# ADL5390board.net
KiCad netlist of a schematic drawn in EAGLE
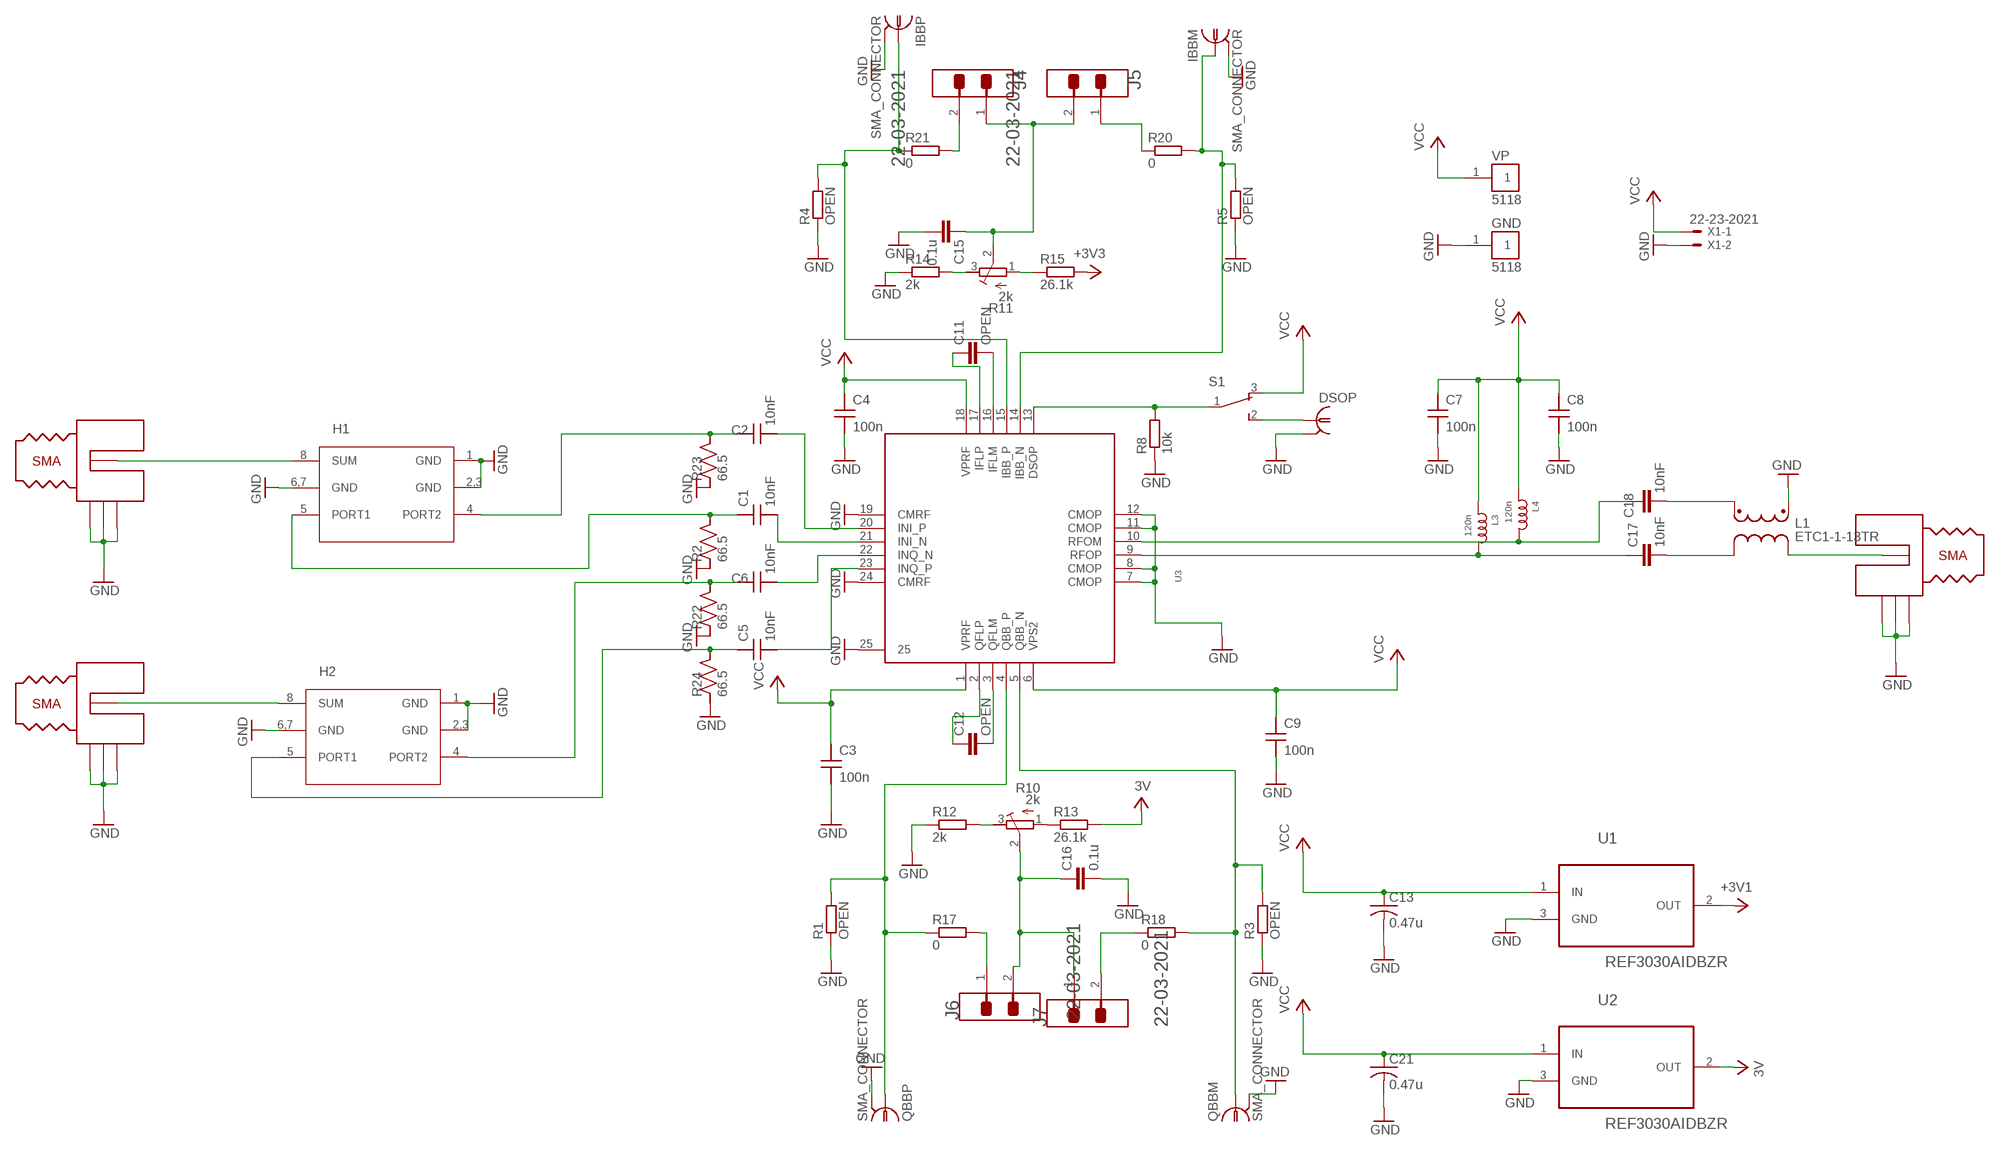
[diagram p0: schematic, sheet 1]

(export (version "E")
  (design (tool "Eeschema 10.0.6"))
  (components
    (comp (ref "C1")
      (value "10nF")
      (footprint "eagle-import:C_MLCC_0402")
      (fields (field (name "PARTNO") "C1005C0G1H102J050BA"))
      (libsource (lib "eagle-import") (part "C_MLCC_SMDCMLCC_0402"))
    )
    (comp (ref "C2")
      (value "10nF")
      (footprint "eagle-import:C_MLCC_0402")
      (fields (field (name "PARTNO") "C1005C0G1H102J050BA"))
      (libsource (lib "eagle-import") (part "C_MLCC_SMDCMLCC_0402"))
    )
    (comp (ref "C3")
      (value "100n")
      (footprint "eagle-import:C_MLCC_0204")
      (fields (field (name "PARTNO") "EWK105C6104MPHF"))
      (libsource (lib "eagle-import") (part "C_MLCC_SMDCMLCC_0204"))
    )
    (comp (ref "C4")
      (value "100n")
      (footprint "eagle-import:C_MLCC_0204")
      (fields (field (name "PARTNO") "EWK105C6104MPHF"))
      (libsource (lib "eagle-import") (part "C_MLCC_SMDCMLCC_0204"))
    )
    (comp (ref "C5")
      (value "10nF")
      (footprint "eagle-import:C_MLCC_0402")
      (fields (field (name "PARTNO") "C1005C0G1H102J050BA"))
      (libsource (lib "eagle-import") (part "C_MLCC_SMDCMLCC_0402"))
    )
    (comp (ref "C6")
      (value "10nF")
      (footprint "eagle-import:C_MLCC_0402")
      (fields (field (name "PARTNO") "C1005C0G1H102J050BA"))
      (libsource (lib "eagle-import") (part "C_MLCC_SMDCMLCC_0402"))
    )
    (comp (ref "C7")
      (value "100n")
      (footprint "eagle-import:C_MLCC_0204")
      (fields (field (name "PARTNO") "EWK105C6104MPHF"))
      (libsource (lib "eagle-import") (part "C_MLCC_SMDCMLCC_0204"))
    )
    (comp (ref "C8")
      (value "100n")
      (footprint "eagle-import:C_MLCC_0204")
      (fields (field (name "PARTNO") "EWK105C6104MPHF"))
      (libsource (lib "eagle-import") (part "C_MLCC_SMDCMLCC_0204"))
    )
    (comp (ref "C9")
      (value "100n")
      (footprint "eagle-import:C_MLCC_0204")
      (fields (field (name "PARTNO") "EWK105C6104MPHF"))
      (libsource (lib "eagle-import") (part "C_MLCC_SMDCMLCC_0204"))
    )
    (comp (ref "C11")
      (value "OPEN")
      (footprint "eagle-import:C0603")
      (libsource (lib "eagle-import") (part "C-EUC0603"))
    )
    (comp (ref "C12")
      (value "OPEN")
      (footprint "eagle-import:C0603")
      (libsource (lib "eagle-import") (part "C-EUC0603"))
    )
    (comp (ref "C13")
      (value "0.47u")
      (footprint "eagle-import:C0603")
      (fields (field (name "PARTNO") "CL10B474KA8NFNC"))
      (libsource (lib "eagle-import") (part "C-USC0603"))
    )
    (comp (ref "C15")
      (value "0.1u")
      (footprint "eagle-import:C0603")
      (fields (field (name "PARTNO") "CL10B104KA8NNNC"))
      (libsource (lib "eagle-import") (part "C-EUC0603"))
    )
    (comp (ref "C16")
      (value "0.1u")
      (footprint "eagle-import:C0603")
      (fields (field (name "PARTNO") "CL10B104KA8NNNC"))
      (libsource (lib "eagle-import") (part "C-EUC0603"))
    )
    (comp (ref "C17")
      (value "10nF")
      (footprint "eagle-import:C0402")
      (fields (field (name "PARTNO") "C1005C0G1H102J050BA"))
      (libsource (lib "eagle-import") (part "C-EUC0402"))
    )
    (comp (ref "C18")
      (value "10nF")
      (footprint "eagle-import:C0402")
      (fields (field (name "PARTNO") "C1005C0G1H102J050BA"))
      (libsource (lib "eagle-import") (part "C-EUC0402"))
    )
    (comp (ref "C21")
      (value "0.47u")
      (footprint "eagle-import:C0603")
      (fields (field (name "PARTNO") "CL10B474KA8NFNC"))
      (libsource (lib "eagle-import") (part "C-USC0603"))
    )
    (comp (ref "DSOP")
      (value "SMA_CONNECTOR")
      (footprint "eagle-import:QKDLAB_JOSH_MECHANICAL_JOHNSON_SMA_EDGE_LAUNCH_142-0701-851")
      (libsource (lib "eagle-import") (part "SMA_CONNECTOR"))
    )
    (comp (ref "GND")
      (value "5118")
      (footprint "eagle-import:TP_5118")
      (fields (field (name "MF") "Keystone Electronics"))
      (libsource (lib "eagle-import") (part "5118"))
    )
    (comp (ref "H1")
      (value "SYPJ-2-33+")
      (footprint "eagle-import:PL-274")
      (libsource (lib "eagle-import") (part "SYPJ-2-33+"))
    )
    (comp (ref "H2")
      (value "SYPJ-2-33+")
      (footprint "eagle-import:PL-274")
      (libsource (lib "eagle-import") (part "SYPJ-2-33+"))
    )
    (comp (ref "IBBM")
      (value "SMA_CONNECTOR")
      (footprint "eagle-import:QKDLAB_JOSH_MECHANICAL_JOHNSON_SMA_EDGE_LAUNCH_142-0701-851")
      (libsource (lib "eagle-import") (part "SMA_CONNECTOR"))
    )
    (comp (ref "IBBP")
      (value "SMA_CONNECTOR")
      (footprint "eagle-import:QKDLAB_JOSH_MECHANICAL_JOHNSON_SMA_EDGE_LAUNCH_142-0701-851")
      (libsource (lib "eagle-import") (part "SMA_CONNECTOR"))
    )
    (comp (ref "J1")
      (value "QKDLAB_JOSH_MECHANICAL_JOHNSON_SMA_18GHZ_142-0761-891")
      (footprint "eagle-import:QKDLAB_JOSH_MECHANICAL_JOHNSON_SMA_18GHZ_4-LAYER_142-0761-891")
      (fields (field (name "PARTNO") "901-10511-2"))
      (libsource (lib "eagle-import") (part "QKDLAB_JOSH_MECHANICAL_JOHNSON_SMA_18GHZ_142-0761-891"))
    )
    (comp (ref "J2")
      (value "QKDLAB_JOSH_MECHANICAL_JOHNSON_SMA_18GHZ_142-0761-891")
      (footprint "eagle-import:QKDLAB_JOSH_MECHANICAL_JOHNSON_SMA_18GHZ_4-LAYER_142-0761-891")
      (fields (field (name "PARTNO") "901-10511-2"))
      (libsource (lib "eagle-import") (part "QKDLAB_JOSH_MECHANICAL_JOHNSON_SMA_18GHZ_142-0761-891"))
    )
    (comp (ref "J3")
      (value "QKDLAB_JOSH_MECHANICAL_JOHNSON_SMA_18GHZ_142-0761-891")
      (footprint "eagle-import:QKDLAB_JOSH_MECHANICAL_JOHNSON_SMA_18GHZ_4-LAYER_142-0761-891")
      (fields (field (name "PARTNO") "901-10511-2"))
      (libsource (lib "eagle-import") (part "QKDLAB_JOSH_MECHANICAL_JOHNSON_SMA_18GHZ_142-0761-891"))
    )
    (comp (ref "J4")
      (value "MOLEX_22-03-2021MOLEX_22-03-2021_0_0")
      (footprint "eagle-import:MOLEX_22-03-2021_0")
      (fields
        (field (name "DIGIKEY_PART_NUMBER") "WM4000-ND")
        (field (name "MF") "Molex")
        (field (name "MOUSER_PART_NUMBER") "538-22-03-2021")
      )
      (libsource (lib "eagle-import") (part "MOLEX_22-03-2021MOLEX_22-03-2021_0_0"))
    )
    (comp (ref "J5")
      (value "MOLEX_22-03-2021MOLEX_22-03-2021_0_0")
      (footprint "eagle-import:MOLEX_22-03-2021_0")
      (fields
        (field (name "DIGIKEY_PART_NUMBER") "WM4000-ND")
        (field (name "MF") "Molex")
        (field (name "MOUSER_PART_NUMBER") "538-22-03-2021")
      )
      (libsource (lib "eagle-import") (part "MOLEX_22-03-2021MOLEX_22-03-2021_0_0"))
    )
    (comp (ref "J6")
      (value "MOLEX_22-03-2021MOLEX_22-03-2021_0_0")
      (footprint "eagle-import:MOLEX_22-03-2021_0")
      (fields
        (field (name "DIGIKEY_PART_NUMBER") "WM4000-ND")
        (field (name "MF") "Molex")
        (field (name "MOUSER_PART_NUMBER") "538-22-03-2021")
      )
      (libsource (lib "eagle-import") (part "MOLEX_22-03-2021MOLEX_22-03-2021_0_0"))
    )
    (comp (ref "J7")
      (value "MOLEX_22-03-2021MOLEX_22-03-2021_0_0")
      (footprint "eagle-import:MOLEX_22-03-2021_0")
      (fields
        (field (name "DIGIKEY_PART_NUMBER") "WM4000-ND")
        (field (name "MF") "Molex")
        (field (name "MOUSER_PART_NUMBER") "538-22-03-2021")
      )
      (libsource (lib "eagle-import") (part "MOLEX_22-03-2021MOLEX_22-03-2021_0_0"))
    )
    (comp (ref "L1")
      (value "ETC1-1-13TR")
      (footprint "eagle-import:SM22")
      (fields (field (name "MF") "M/A-Com Technology"))
      (libsource (lib "eagle-import") (part "ETC1-1-13TR"))
    )
    (comp (ref "L3")
      (value "120n")
      (footprint "eagle-import:R0603")
      (fields (field (name "PARTNO") "LQW18ASR12G0CD"))
      (libsource (lib "eagle-import") (part "L_0603"))
    )
    (comp (ref "L4")
      (value "120n")
      (footprint "eagle-import:R0603")
      (fields (field (name "PARTNO") "LQW18ASR12G0CD"))
      (libsource (lib "eagle-import") (part "L_0603"))
    )
    (comp (ref "QBBM")
      (value "SMA_CONNECTOR")
      (footprint "eagle-import:QKDLAB_JOSH_MECHANICAL_JOHNSON_SMA_EDGE_LAUNCH_142-0701-851")
      (libsource (lib "eagle-import") (part "SMA_CONNECTOR"))
    )
    (comp (ref "QBBP")
      (value "SMA_CONNECTOR")
      (footprint "eagle-import:QKDLAB_JOSH_MECHANICAL_JOHNSON_SMA_EDGE_LAUNCH_142-0701-851")
      (libsource (lib "eagle-import") (part "SMA_CONNECTOR"))
    )
    (comp (ref "R1")
      (value "OPEN")
      (footprint "eagle-import:R0603")
      (fields (field (name "PARTNO") "CRCW06030000Z0EA"))
      (libsource (lib "eagle-import") (part "R-EU_R0603"))
    )
    (comp (ref "R2")
      (value "66.5")
      (footprint "eagle-import:R_0402")
      (fields (field (name "PARTNO") "ERJ-2RKF66R5X"))
      (libsource (lib "eagle-import") (part "R_SMDR0402"))
    )
    (comp (ref "R3")
      (value "OPEN")
      (footprint "eagle-import:R0603")
      (fields (field (name "PARTNO") "CRCW06030000Z0EA"))
      (libsource (lib "eagle-import") (part "R-EU_R0603"))
    )
    (comp (ref "R4")
      (value "OPEN")
      (footprint "eagle-import:R0603")
      (fields (field (name "PARTNO") "CRCW06030000Z0EA"))
      (libsource (lib "eagle-import") (part "R-EU_R0603"))
    )
    (comp (ref "R5")
      (value "OPEN")
      (footprint "eagle-import:R0603")
      (fields (field (name "PARTNO") "CRCW06030000Z0EA"))
      (libsource (lib "eagle-import") (part "R-EU_R0603"))
    )
    (comp (ref "R8")
      (value "10k")
      (footprint "eagle-import:R0603")
      (fields (field (name "PARTNO") "ERA-3AEB103V"))
      (libsource (lib "eagle-import") (part "R-EU_R0603"))
    )
    (comp (ref "R10")
      (value "2k")
      (footprint "eagle-import:RTRIM3296W")
      (fields (field (name "PARTNO") "PV36W202C01B00"))
      (libsource (lib "eagle-import") (part "R-TRIMM3296W"))
    )
    (comp (ref "R11")
      (value "2k")
      (footprint "eagle-import:RTRIM3296W")
      (fields (field (name "PARTNO") "PV36W202C01B00"))
      (libsource (lib "eagle-import") (part "R-TRIMM3296W"))
    )
    (comp (ref "R12")
      (value "2k")
      (footprint "eagle-import:R0603")
      (fields (field (name "PARTNO") "ERA-3AEB202V"))
      (libsource (lib "eagle-import") (part "R-EU_R0603"))
    )
    (comp (ref "R13")
      (value "26.1k")
      (footprint "eagle-import:R0603")
      (fields (field (name "PARTNO") "ERA-3AEB2612V"))
      (libsource (lib "eagle-import") (part "R-EU_R0603"))
    )
    (comp (ref "R14")
      (value "2k")
      (footprint "eagle-import:R0603")
      (fields (field (name "PARTNO") "ERA-3AEB202V"))
      (libsource (lib "eagle-import") (part "R-EU_R0603"))
    )
    (comp (ref "R15")
      (value "26.1k")
      (footprint "eagle-import:R0603")
      (fields (field (name "PARTNO") "ERA-3AEB2612V"))
      (libsource (lib "eagle-import") (part "R-EU_R0603"))
    )
    (comp (ref "R17")
      (value "0")
      (footprint "eagle-import:R0603")
      (fields (field (name "PARTNO") "CRCW06030000Z0EA"))
      (libsource (lib "eagle-import") (part "R-EU_R0603"))
    )
    (comp (ref "R18")
      (value "0")
      (footprint "eagle-import:R0603")
      (fields (field (name "PARTNO") "CRCW06030000Z0EA"))
      (libsource (lib "eagle-import") (part "R-EU_R0603"))
    )
    (comp (ref "R20")
      (value "0")
      (footprint "eagle-import:R0603")
      (fields (field (name "PARTNO") "CRCW06030000Z0EA"))
      (libsource (lib "eagle-import") (part "R-EU_R0603"))
    )
    (comp (ref "R21")
      (value "0")
      (footprint "eagle-import:R0603")
      (fields (field (name "PARTNO") "CRCW06030000Z0EA"))
      (libsource (lib "eagle-import") (part "R-EU_R0603"))
    )
    (comp (ref "R22")
      (value "66.5")
      (footprint "eagle-import:R_0402")
      (fields (field (name "PARTNO") "ERJ-2RKF66R5X"))
      (libsource (lib "eagle-import") (part "R_SMDR0402"))
    )
    (comp (ref "R23")
      (value "66.5")
      (footprint "eagle-import:R_0402")
      (fields (field (name "PARTNO") "ERJ-2RKF66R5X"))
      (libsource (lib "eagle-import") (part "R_SMDR0402"))
    )
    (comp (ref "R24")
      (value "66.5")
      (footprint "eagle-import:R_0402")
      (fields (field (name "PARTNO") "ERJ-2RKF66R5X"))
      (libsource (lib "eagle-import") (part "R_SMDR0402"))
    )
    (comp (ref "S1")
      (value "450301014042")
      (footprint "eagle-import:450301014042")
      (fields (field (name "MF") "Wurth Electronics"))
      (libsource (lib "eagle-import") (part "450301014042"))
    )
    (comp (ref "U1")
      (value "REF3030AIDBZR")
      (footprint "eagle-import:SOT95P237X112-3N")
      (fields (field (name "DIGI-KEY_PART_NUMBER") "296-26323-1-ND") (field (name "MF") "Texas Instruments"))
      (libsource (lib "eagle-import") (part "REF3030AIDBZR"))
    )
    (comp (ref "U2")
      (value "REF3030AIDBZR")
      (footprint "eagle-import:SOT95P237X112-3N")
      (fields (field (name "DIGI-KEY_PART_NUMBER") "296-26323-1-ND") (field (name "MF") "Texas Instruments"))
      (libsource (lib "eagle-import") (part "REF3030AIDBZR"))
    )
    (comp (ref "U3")
      (value "ADL5390_ADL5390")
      (footprint "eagle-import:ADL5390_ADL5390")
      (fields (field (name "PARTNO") "ADL5390ACPZ-REEL7"))
      (libsource (lib "eagle-import") (part "ADL5390_ADL5390"))
    )
    (comp (ref "VP")
      (value "5118")
      (footprint "eagle-import:TP_5118")
      (fields (field (name "MF") "Keystone Electronics") (field (name "PARTNO") "5000"))
      (libsource (lib "eagle-import") (part "5118"))
    )
    (comp (ref "X1")
      (value "22-23-2021")
      (footprint "eagle-import:22-23-2021")
      (fields (field (name "MF") "MOLEX"))
      (libsource (lib "eagle-import") (part "22-23-2021"))
    )
  )
  (nets
    (net (code "1") (name "+3V1") (class "Default")
      (node (ref "R15") (pin "2") (pinfunction "2_2") (pintype "passive"))
      (node (ref "U1") (pin "2") (pinfunction "OUT_2") (pintype "output"))
    )
    (net (code "2") (name "3V") (class "Default")
      (node (ref "R13") (pin "2") (pinfunction "2_2") (pintype "passive"))
      (node (ref "U2") (pin "2") (pinfunction "OUT_2") (pintype "output"))
    )
    (net (code "3") (name "GND") (class "Default")
      (node (ref "C13") (pin "2") (pinfunction "2_2") (pintype "passive"))
      (node (ref "C15") (pin "2") (pinfunction "2_2") (pintype "passive"))
      (node (ref "C16") (pin "2") (pinfunction "2_2") (pintype "passive"))
      (node (ref "C21") (pin "2") (pinfunction "2_2") (pintype "passive"))
      (node (ref "C3") (pin "P$2") (pinfunction "2_P$2") (pintype "passive"))
      (node (ref "C4") (pin "P$2") (pinfunction "2_P$2") (pintype "passive"))
      (node (ref "C7") (pin "P$2") (pinfunction "2_P$2") (pintype "passive"))
      (node (ref "C8") (pin "P$2") (pinfunction "2_P$2") (pintype "passive"))
      (node (ref "C9") (pin "P$2") (pinfunction "2_P$2") (pintype "passive"))
      (node (ref "DSOP") (pin "P$2") (pinfunction "2_P$2") (pintype "passive"))
      (node (ref "DSOP") (pin "P$3") (pinfunction "2_P$3") (pintype "passive"))
      (node (ref "DSOP") (pin "P$4") (pinfunction "2_P$4") (pintype "passive"))
      (node (ref "DSOP") (pin "P$5") (pinfunction "2_P$5") (pintype "passive"))
      (node (ref "GND") (pin "1") (pinfunction "1_1") (pintype "passive"))
      (node (ref "H1") (pin "1") (pinfunction "GND_1") (pintype "bidirectional"))
      (node (ref "H1") (pin "2,3") (pinfunction "GND_2,3") (pintype "bidirectional"))
      (node (ref "H1") (pin "6,7") (pinfunction "GND_6,7") (pintype "bidirectional"))
      (node (ref "H2") (pin "1") (pinfunction "GND_1") (pintype "bidirectional"))
      (node (ref "H2") (pin "2,3") (pinfunction "GND_2,3") (pintype "bidirectional"))
      (node (ref "H2") (pin "6,7") (pinfunction "GND_6,7") (pintype "bidirectional"))
      (node (ref "IBBM") (pin "P$2") (pinfunction "2_P$2") (pintype "passive"))
      (node (ref "IBBM") (pin "P$3") (pinfunction "2_P$3") (pintype "passive"))
      (node (ref "IBBM") (pin "P$4") (pinfunction "2_P$4") (pintype "passive"))
      (node (ref "IBBM") (pin "P$5") (pinfunction "2_P$5") (pintype "passive"))
      (node (ref "IBBP") (pin "P$2") (pinfunction "2_P$2") (pintype "passive"))
      (node (ref "IBBP") (pin "P$3") (pinfunction "2_P$3") (pintype "passive"))
      (node (ref "IBBP") (pin "P$4") (pinfunction "2_P$4") (pintype "passive"))
      (node (ref "IBBP") (pin "P$5") (pinfunction "2_P$5") (pintype "passive"))
      (node (ref "J1") (pin "P$2") (pinfunction "GND_P$2") (pintype "bidirectional"))
      (node (ref "J1") (pin "P$3") (pinfunction "GND_P$3") (pintype "bidirectional"))
      (node (ref "J1") (pin "P$4") (pinfunction "GND_P$4") (pintype "bidirectional"))
      (node (ref "J2") (pin "P$2") (pinfunction "GND_P$2") (pintype "bidirectional"))
      (node (ref "J2") (pin "P$3") (pinfunction "GND_P$3") (pintype "bidirectional"))
      (node (ref "J2") (pin "P$4") (pinfunction "GND_P$4") (pintype "bidirectional"))
      (node (ref "J3") (pin "P$2") (pinfunction "GND_P$2") (pintype "bidirectional"))
      (node (ref "J3") (pin "P$3") (pinfunction "GND_P$3") (pintype "bidirectional"))
      (node (ref "J3") (pin "P$4") (pinfunction "GND_P$4") (pintype "bidirectional"))
      (node (ref "L1") (pin "1") (pinfunction "1_1") (pintype "passive"))
      (node (ref "QBBM") (pin "P$2") (pinfunction "2_P$2") (pintype "passive"))
      (node (ref "QBBM") (pin "P$3") (pinfunction "2_P$3") (pintype "passive"))
      (node (ref "QBBM") (pin "P$4") (pinfunction "2_P$4") (pintype "passive"))
      (node (ref "QBBM") (pin "P$5") (pinfunction "2_P$5") (pintype "passive"))
      (node (ref "QBBP") (pin "P$2") (pinfunction "2_P$2") (pintype "passive"))
      (node (ref "QBBP") (pin "P$3") (pinfunction "2_P$3") (pintype "passive"))
      (node (ref "QBBP") (pin "P$4") (pinfunction "2_P$4") (pintype "passive"))
      (node (ref "QBBP") (pin "P$5") (pinfunction "2_P$5") (pintype "passive"))
      (node (ref "R1") (pin "1") (pinfunction "1_1") (pintype "passive"))
      (node (ref "R12") (pin "1") (pinfunction "1_1") (pintype "passive"))
      (node (ref "R14") (pin "1") (pinfunction "1_1") (pintype "passive"))
      (node (ref "R2") (pin "P$1") (pinfunction "1_P$1") (pintype "passive"))
      (node (ref "R22") (pin "P$1") (pinfunction "1_P$1") (pintype "passive"))
      (node (ref "R23") (pin "P$1") (pinfunction "1_P$1") (pintype "passive"))
      (node (ref "R24") (pin "P$1") (pinfunction "1_P$1") (pintype "passive"))
      (node (ref "R3") (pin "1") (pinfunction "1_1") (pintype "passive"))
      (node (ref "R4") (pin "1") (pinfunction "1_1") (pintype "passive"))
      (node (ref "R5") (pin "1") (pinfunction "1_1") (pintype "passive"))
      (node (ref "R8") (pin "1") (pinfunction "1_1") (pintype "passive"))
      (node (ref "U1") (pin "3") (pinfunction "GND_3") (pintype "passive"))
      (node (ref "U2") (pin "3") (pinfunction "GND_3") (pintype "passive"))
      (node (ref "U3") (pin "11") (pinfunction "CMOP_11") (pintype "bidirectional"))
      (node (ref "U3") (pin "12") (pinfunction "CMOP_12") (pintype "bidirectional"))
      (node (ref "U3") (pin "19") (pinfunction "CMRF_19") (pintype "bidirectional"))
      (node (ref "U3") (pin "24") (pinfunction "CMRF_24") (pintype "bidirectional"))
      (node (ref "U3") (pin "25") (pinfunction "25_25") (pintype "bidirectional"))
      (node (ref "U3") (pin "7") (pinfunction "CMOP_7") (pintype "bidirectional"))
      (node (ref "U3") (pin "8") (pinfunction "CMOP_8") (pintype "bidirectional"))
      (node (ref "X1") (pin "2") (pinfunction "S_2") (pintype "passive"))
    )
    (net (code "4") (name "Net-(C1-1)") (class "Default")
      (node (ref "C1") (pin "P$1") (pinfunction "1_P$1") (pintype "passive"))
      (node (ref "H1") (pin "5") (pinfunction "PORT1_5") (pintype "bidirectional"))
      (node (ref "R2") (pin "P$2") (pinfunction "2_P$2") (pintype "passive"))
    )
    (net (code "5") (name "Net-(C1-2)") (class "Default")
      (node (ref "C1") (pin "P$2") (pinfunction "2_P$2") (pintype "passive"))
      (node (ref "U3") (pin "21") (pinfunction "INI_N_21") (pintype "bidirectional"))
    )
    (net (code "6") (name "Net-(C2-1)") (class "Default")
      (node (ref "C2") (pin "P$1") (pinfunction "1_P$1") (pintype "passive"))
      (node (ref "H1") (pin "4") (pinfunction "PORT2_4") (pintype "bidirectional"))
      (node (ref "R23") (pin "P$2") (pinfunction "2_P$2") (pintype "passive"))
    )
    (net (code "7") (name "Net-(C2-2)") (class "Default")
      (node (ref "C2") (pin "P$2") (pinfunction "2_P$2") (pintype "passive"))
      (node (ref "U3") (pin "20") (pinfunction "INI_P_20") (pintype "bidirectional"))
    )
    (net (code "8") (name "Net-(C5-1)") (class "Default")
      (node (ref "C5") (pin "P$1") (pinfunction "1_P$1") (pintype "passive"))
      (node (ref "H2") (pin "5") (pinfunction "PORT1_5") (pintype "bidirectional"))
      (node (ref "R24") (pin "P$2") (pinfunction "2_P$2") (pintype "passive"))
    )
    (net (code "9") (name "Net-(C5-2)") (class "Default")
      (node (ref "C5") (pin "P$2") (pinfunction "2_P$2") (pintype "passive"))
      (node (ref "U3") (pin "23") (pinfunction "INQ_P_23") (pintype "bidirectional"))
    )
    (net (code "10") (name "Net-(C6-1)") (class "Default")
      (node (ref "C6") (pin "P$1") (pinfunction "1_P$1") (pintype "passive"))
      (node (ref "H2") (pin "4") (pinfunction "PORT2_4") (pintype "bidirectional"))
      (node (ref "R22") (pin "P$2") (pinfunction "2_P$2") (pintype "passive"))
    )
    (net (code "11") (name "Net-(C6-2)") (class "Default")
      (node (ref "C6") (pin "P$2") (pinfunction "2_P$2") (pintype "passive"))
      (node (ref "U3") (pin "22") (pinfunction "INQ_N_22") (pintype "bidirectional"))
    )
    (net (code "12") (name "Net-(C17-Pad2)") (class "Default")
      (node (ref "C17") (pin "2") (pinfunction "2_2") (pintype "passive"))
      (node (ref "L1") (pin "4") (pinfunction "4_4") (pintype "passive"))
    )
    (net (code "13") (name "Net-(C18-Pad2)") (class "Default")
      (node (ref "C18") (pin "2") (pinfunction "2_2") (pintype "passive"))
      (node (ref "L1") (pin "5") (pinfunction "5_5") (pintype "passive"))
    )
    (net (code "14") (name "Net-(DSOP-1)") (class "Default")
      (node (ref "DSOP") (pin "P$1") (pinfunction "1_P$1") (pintype "passive"))
      (node (ref "S1") (pin "2") (pinfunction "2_2") (pintype "passive"))
    )
    (net (code "15") (name "Net-(H1-SUM)") (class "Default")
      (node (ref "H1") (pin "8") (pinfunction "SUM_8") (pintype "bidirectional"))
      (node (ref "J1") (pin "P$1") (pinfunction "SIG_P$1") (pintype "bidirectional"))
    )
    (net (code "16") (name "Net-(H2-SUM)") (class "Default")
      (node (ref "H2") (pin "8") (pinfunction "SUM_8") (pintype "bidirectional"))
      (node (ref "J2") (pin "P$1") (pinfunction "SIG_P$1") (pintype "bidirectional"))
    )
    (net (code "17") (name "Net-(IBBM-1)") (class "Default")
      (node (ref "IBBM") (pin "P$1") (pinfunction "1_P$1") (pintype "passive"))
      (node (ref "R20") (pin "2") (pinfunction "2_2") (pintype "passive"))
      (node (ref "R5") (pin "2") (pinfunction "2_2") (pintype "passive"))
      (node (ref "U3") (pin "14") (pinfunction "IBB_N_14") (pintype "bidirectional"))
    )
    (net (code "18") (name "Net-(IBBP-1)") (class "Default")
      (node (ref "IBBP") (pin "P$1") (pinfunction "1_P$1") (pintype "passive"))
      (node (ref "R21") (pin "1") (pinfunction "1_1") (pintype "passive"))
      (node (ref "R4") (pin "2") (pinfunction "2_2") (pintype "passive"))
      (node (ref "U3") (pin "15") (pinfunction "IBB_P_15") (pintype "bidirectional"))
    )
    (net (code "19") (name "Net-(J3-SIG)") (class "Default")
      (node (ref "J3") (pin "P$1") (pinfunction "SIG_P$1") (pintype "bidirectional"))
      (node (ref "L1") (pin "3") (pinfunction "3_3") (pintype "passive"))
    )
    (net (code "20") (name "Net-(J4-Pad2)") (class "Default")
      (node (ref "J4") (pin "2") (pinfunction "2_2") (pintype "bidirectional"))
      (node (ref "R21") (pin "2") (pinfunction "2_2") (pintype "passive"))
    )
    (net (code "21") (name "Net-(J5-Pad1)") (class "Default")
      (node (ref "J5") (pin "1") (pinfunction "1_1") (pintype "bidirectional"))
      (node (ref "R20") (pin "1") (pinfunction "1_1") (pintype "passive"))
    )
    (net (code "22") (name "Net-(J6-Pad1)") (class "Default")
      (node (ref "J6") (pin "1") (pinfunction "1_1") (pintype "bidirectional"))
      (node (ref "R17") (pin "2") (pinfunction "2_2") (pintype "passive"))
    )
    (net (code "23") (name "Net-(J7-Pad2)") (class "Default")
      (node (ref "J7") (pin "2") (pinfunction "2_2") (pintype "bidirectional"))
      (node (ref "R18") (pin "1") (pinfunction "1_1") (pintype "passive"))
    )
    (net (code "24") (name "Net-(L3-P$2)") (class "Default")
      (node (ref "C17") (pin "1") (pinfunction "1_1") (pintype "passive"))
      (node (ref "L3") (pin "2") (pinfunction "P$2_2") (pintype "passive"))
      (node (ref "U3") (pin "9") (pinfunction "RFOP_9") (pintype "bidirectional"))
    )
    (net (code "25") (name "Net-(L4-P$2)") (class "Default")
      (node (ref "C18") (pin "1") (pinfunction "1_1") (pintype "passive"))
      (node (ref "L4") (pin "2") (pinfunction "P$2_2") (pintype "passive"))
      (node (ref "U3") (pin "10") (pinfunction "RFOM_10") (pintype "bidirectional"))
    )
    (net (code "26") (name "Net-(QBBM-1)") (class "Default")
      (node (ref "QBBM") (pin "P$1") (pinfunction "1_P$1") (pintype "passive"))
      (node (ref "R18") (pin "2") (pinfunction "2_2") (pintype "passive"))
      (node (ref "R3") (pin "2") (pinfunction "2_2") (pintype "passive"))
      (node (ref "U3") (pin "5") (pinfunction "QBB_N_5") (pintype "bidirectional"))
    )
    (net (code "27") (name "Net-(QBBP-1)") (class "Default")
      (node (ref "QBBP") (pin "P$1") (pinfunction "1_P$1") (pintype "passive"))
      (node (ref "R1") (pin "2") (pinfunction "2_2") (pintype "passive"))
      (node (ref "R17") (pin "1") (pinfunction "1_1") (pintype "passive"))
      (node (ref "U3") (pin "4") (pinfunction "QBB_P_4") (pintype "bidirectional"))
    )
    (net (code "28") (name "Net-(R10-A)") (class "Default")
      (node (ref "R10") (pin "1") (pinfunction "A_1") (pintype "passive"))
      (node (ref "R13") (pin "1") (pinfunction "1_1") (pintype "passive"))
    )
    (net (code "29") (name "Net-(R10-E)") (class "Default")
      (node (ref "R10") (pin "3") (pinfunction "E_3") (pintype "passive"))
      (node (ref "R12") (pin "2") (pinfunction "2_2") (pintype "passive"))
    )
    (net (code "30") (name "Net-(R10-S)") (class "Default")
      (node (ref "C16") (pin "1") (pinfunction "1_1") (pintype "passive"))
      (node (ref "J6") (pin "2") (pinfunction "2_2") (pintype "bidirectional"))
      (node (ref "J7") (pin "1") (pinfunction "1_1") (pintype "bidirectional"))
      (node (ref "R10") (pin "2") (pinfunction "S_2") (pintype "passive"))
    )
    (net (code "31") (name "Net-(R11-A)") (class "Default")
      (node (ref "R11") (pin "1") (pinfunction "A_1") (pintype "passive"))
      (node (ref "R15") (pin "1") (pinfunction "1_1") (pintype "passive"))
    )
    (net (code "32") (name "Net-(R11-E)") (class "Default")
      (node (ref "R11") (pin "3") (pinfunction "E_3") (pintype "passive"))
      (node (ref "R14") (pin "2") (pinfunction "2_2") (pintype "passive"))
    )
    (net (code "33") (name "Net-(R11-S)") (class "Default")
      (node (ref "C15") (pin "1") (pinfunction "1_1") (pintype "passive"))
      (node (ref "J4") (pin "1") (pinfunction "1_1") (pintype "bidirectional"))
      (node (ref "J5") (pin "2") (pinfunction "2_2") (pintype "bidirectional"))
      (node (ref "R11") (pin "2") (pinfunction "S_2") (pintype "passive"))
    )
    (net (code "34") (name "Net-(U3-DSOP)") (class "Default")
      (node (ref "R8") (pin "2") (pinfunction "2_2") (pintype "passive"))
      (node (ref "S1") (pin "1") (pinfunction "1_1") (pintype "passive"))
      (node (ref "U3") (pin "13") (pinfunction "DSOP_13") (pintype "bidirectional"))
    )
    (net (code "35") (name "Net-(U3-IFLM)") (class "Default")
      (node (ref "C11") (pin "2") (pinfunction "2_2") (pintype "passive"))
      (node (ref "U3") (pin "16") (pinfunction "IFLM_16") (pintype "bidirectional"))
    )
    (net (code "36") (name "Net-(U3-IFLP)") (class "Default")
      (node (ref "C11") (pin "1") (pinfunction "1_1") (pintype "passive"))
      (node (ref "U3") (pin "17") (pinfunction "IFLP_17") (pintype "bidirectional"))
    )
    (net (code "37") (name "Net-(U3-QFLM)") (class "Default")
      (node (ref "C12") (pin "2") (pinfunction "2_2") (pintype "passive"))
      (node (ref "U3") (pin "3") (pinfunction "QFLM_3") (pintype "bidirectional"))
    )
    (net (code "38") (name "Net-(U3-QFLP)") (class "Default")
      (node (ref "C12") (pin "1") (pinfunction "1_1") (pintype "passive"))
      (node (ref "U3") (pin "2") (pinfunction "QFLP_2") (pintype "bidirectional"))
    )
    (net (code "39") (name "VCC") (class "Default")
      (node (ref "C13") (pin "1") (pinfunction "1_1") (pintype "passive"))
      (node (ref "C21") (pin "1") (pinfunction "1_1") (pintype "passive"))
      (node (ref "C3") (pin "P$1") (pinfunction "1_P$1") (pintype "passive"))
      (node (ref "C4") (pin "P$1") (pinfunction "1_P$1") (pintype "passive"))
      (node (ref "C7") (pin "P$1") (pinfunction "1_P$1") (pintype "passive"))
      (node (ref "C8") (pin "P$1") (pinfunction "1_P$1") (pintype "passive"))
      (node (ref "C9") (pin "P$1") (pinfunction "1_P$1") (pintype "passive"))
      (node (ref "L3") (pin "1") (pinfunction "P$1_1") (pintype "passive"))
      (node (ref "L4") (pin "1") (pinfunction "P$1_1") (pintype "passive"))
      (node (ref "S1") (pin "3") (pinfunction "3_3") (pintype "passive"))
      (node (ref "U1") (pin "1") (pinfunction "IN_1") (pintype "power_in"))
      (node (ref "U2") (pin "1") (pinfunction "IN_1") (pintype "power_in"))
      (node (ref "U3") (pin "1") (pinfunction "VPRF_1") (pintype "bidirectional"))
      (node (ref "U3") (pin "18") (pinfunction "VPRF_18") (pintype "bidirectional"))
      (node (ref "U3") (pin "6") (pinfunction "VPS2_6") (pintype "bidirectional"))
      (node (ref "VP") (pin "1") (pinfunction "1_1") (pintype "passive"))
      (node (ref "X1") (pin "1") (pinfunction "S_1") (pintype "passive"))
    )
  )
)
